# snes-bt.net
KiCad netlist of a schematic drawn in EAGLE
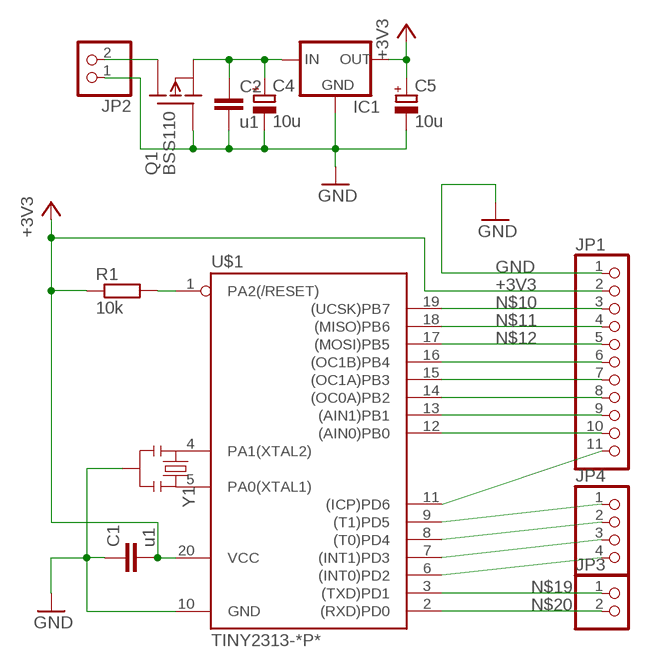
[diagram p0: schematic, sheet 1]

(export (version "E")
  (design (tool "Eeschema 10.0.6"))
  (components
    (comp (ref "C1")
      (value "u1")
      (footprint "eagle-import:C025-025X050")
      (libsource (lib "eagle-import") (part "C-EU025-025X050"))
    )
    (comp (ref "C2")
      (value "u1")
      (footprint "eagle-import:C025-025X050")
      (libsource (lib "eagle-import") (part "C-EU025-025X050"))
    )
    (comp (ref "C4")
      (value "10u")
      (footprint "eagle-import:E2,5-6E")
      (libsource (lib "eagle-import") (part "CPOL-EUE2,5-6E"))
    )
    (comp (ref "C5")
      (value "10u")
      (footprint "eagle-import:E2,5-6E")
      (libsource (lib "eagle-import") (part "CPOL-EUE2,5-6E"))
    )
    (comp (ref "IC1")
      (value "MCP1700_TO92-THIN")
      (footprint "eagle-import:TO-92")
      (libsource (lib "eagle-import") (part "MCP1700_TO92-THIN"))
    )
    (comp (ref "JP1")
      (value "PINHD-1X11")
      (footprint "eagle-import:1X11")
      (libsource (lib "eagle-import") (part "PINHD-1X11"))
    )
    (comp (ref "JP2")
      (value "PINHD-1X2")
      (footprint "eagle-import:1X02")
      (libsource (lib "eagle-import") (part "PINHD-1X2"))
    )
    (comp (ref "JP3")
      (value "PINHD-1X2")
      (footprint "eagle-import:1X02")
      (libsource (lib "eagle-import") (part "PINHD-1X2"))
    )
    (comp (ref "JP4")
      (value "PINHD-1X4")
      (footprint "eagle-import:1X04")
      (libsource (lib "eagle-import") (part "PINHD-1X4"))
    )
    (comp (ref "Q1")
      (value "BSS110")
      (footprint "eagle-import:TO92")
      (libsource (lib "eagle-import") (part "BSS110"))
    )
    (comp (ref "R1")
      (value "10k")
      (footprint "eagle-import:0204_7")
      (libsource (lib "eagle-import") (part "R-EU_0204/7"))
    )
    (comp (ref "U$1")
      (value "TINY2313-*P*")
      (footprint "eagle-import:DIL20")
      (libsource (lib "eagle-import") (part "TINY2313-P"))
    )
    (comp (ref "Y1")
      (value "RESONATORPTH")
      (footprint "eagle-import:RESONATOR-PTH")
      (libsource (lib "eagle-import") (part "RESONATORPTH"))
    )
  )
  (nets
    (net (code "1") (name "+3V3") (class "Default")
      (node (ref "C1") (pin "2") (pinfunction "2_2") (pintype "passive"))
      (node (ref "C5") (pin "+") (pinfunction "+_+") (pintype "passive"))
      (node (ref "IC1") (pin "3") (pinfunction "OUT_3") (pintype "passive"))
      (node (ref "JP1") (pin "2") (pinfunction "2_2") (pintype "passive"))
      (node (ref "R1") (pin "1") (pinfunction "1_1") (pintype "passive"))
      (node (ref "U$1") (pin "20") (pinfunction "VCC_20") (pintype "power_in"))
    )
    (net (code "2") (name "/N$10") (class "Default")
      (node (ref "JP1") (pin "3") (pinfunction "3_3") (pintype "passive"))
      (node (ref "U$1") (pin "19") (pinfunction "(UCSK)PB7_19") (pintype "bidirectional"))
    )
    (net (code "3") (name "/N$11") (class "Default")
      (node (ref "JP1") (pin "4") (pinfunction "4_4") (pintype "passive"))
      (node (ref "U$1") (pin "18") (pinfunction "(MISO)PB6_18") (pintype "bidirectional"))
    )
    (net (code "4") (name "/N$12") (class "Default")
      (node (ref "JP1") (pin "5") (pinfunction "5_5") (pintype "passive"))
      (node (ref "U$1") (pin "17") (pinfunction "(MOSI)PB5_17") (pintype "bidirectional"))
    )
    (net (code "5") (name "/N$19") (class "Default")
      (node (ref "JP3") (pin "1") (pinfunction "1_1") (pintype "passive"))
      (node (ref "U$1") (pin "3") (pinfunction "(TXD)PD1_3") (pintype "bidirectional"))
    )
    (net (code "6") (name "/N$20") (class "Default")
      (node (ref "JP3") (pin "2") (pinfunction "2_2") (pintype "passive"))
      (node (ref "U$1") (pin "2") (pinfunction "(RXD)PD0_2") (pintype "bidirectional"))
    )
    (net (code "7") (name "GND") (class "Default")
      (node (ref "C1") (pin "1") (pinfunction "1_1") (pintype "passive"))
      (node (ref "C2") (pin "2") (pinfunction "2_2") (pintype "passive"))
      (node (ref "C4") (pin "-") (pinfunction "-_-") (pintype "passive"))
      (node (ref "C5") (pin "-") (pinfunction "-_-") (pintype "passive"))
      (node (ref "IC1") (pin "1") (pinfunction "GND_1") (pintype "input"))
      (node (ref "JP1") (pin "1") (pinfunction "1_1") (pintype "passive"))
      (node (ref "JP2") (pin "1") (pinfunction "1_1") (pintype "passive"))
      (node (ref "Q1") (pin "2") (pinfunction "G_2") (pintype "passive"))
      (node (ref "U$1") (pin "10") (pinfunction "GND_10") (pintype "power_in"))
      (node (ref "Y1") (pin "2") (pinfunction "2_2") (pintype "passive"))
    )
    (net (code "8") (name "Net-(IC1-IN)") (class "Default")
      (node (ref "C2") (pin "1") (pinfunction "1_1") (pintype "passive"))
      (node (ref "C4") (pin "+") (pinfunction "+_+") (pintype "passive"))
      (node (ref "IC1") (pin "2") (pinfunction "IN_2") (pintype "input"))
      (node (ref "Q1") (pin "1") (pinfunction "S_1") (pintype "passive"))
    )
    (net (code "9") (name "Net-(Q1-D)") (class "Default")
      (node (ref "JP2") (pin "2") (pinfunction "2_2") (pintype "passive"))
      (node (ref "Q1") (pin "3") (pinfunction "D_3") (pintype "passive"))
    )
    (net (code "10") (name "Net-(U$1-(AIN0)PB0)") (class "Default")
      (node (ref "JP1") (pin "10") (pinfunction "10_10") (pintype "passive"))
      (node (ref "U$1") (pin "12") (pinfunction "(AIN0)PB0_12") (pintype "bidirectional"))
    )
    (net (code "11") (name "Net-(U$1-(AIN1)PB1)") (class "Default")
      (node (ref "JP1") (pin "9") (pinfunction "9_9") (pintype "passive"))
      (node (ref "U$1") (pin "13") (pinfunction "(AIN1)PB1_13") (pintype "bidirectional"))
    )
    (net (code "12") (name "Net-(U$1-(ICP)PD6)") (class "Default")
      (node (ref "JP1") (pin "11") (pinfunction "11_11") (pintype "passive"))
      (node (ref "U$1") (pin "11") (pinfunction "(ICP)PD6_11") (pintype "bidirectional"))
    )
    (net (code "13") (name "Net-(U$1-(INT0)PD2)") (class "Default")
      (node (ref "JP4") (pin "4") (pinfunction "4_4") (pintype "passive"))
      (node (ref "U$1") (pin "6") (pinfunction "(INT0)PD2_6") (pintype "bidirectional"))
    )
    (net (code "14") (name "Net-(U$1-(INT1)PD3)") (class "Default")
      (node (ref "JP4") (pin "3") (pinfunction "3_3") (pintype "passive"))
      (node (ref "U$1") (pin "7") (pinfunction "(INT1)PD3_7") (pintype "bidirectional"))
    )
    (net (code "15") (name "Net-(U$1-(OC0A)PB2)") (class "Default")
      (node (ref "JP1") (pin "8") (pinfunction "8_8") (pintype "passive"))
      (node (ref "U$1") (pin "14") (pinfunction "(OC0A)PB2_14") (pintype "bidirectional"))
    )
    (net (code "16") (name "Net-(U$1-(OC1A)PB3)") (class "Default")
      (node (ref "JP1") (pin "7") (pinfunction "7_7") (pintype "passive"))
      (node (ref "U$1") (pin "15") (pinfunction "(OC1A)PB3_15") (pintype "bidirectional"))
    )
    (net (code "17") (name "Net-(U$1-(OC1B)PB4)") (class "Default")
      (node (ref "JP1") (pin "6") (pinfunction "6_6") (pintype "passive"))
      (node (ref "U$1") (pin "16") (pinfunction "(OC1B)PB4_16") (pintype "bidirectional"))
    )
    (net (code "18") (name "Net-(U$1-(T0)PD4)") (class "Default")
      (node (ref "JP4") (pin "2") (pinfunction "2_2") (pintype "passive"))
      (node (ref "U$1") (pin "8") (pinfunction "(T0)PD4_8") (pintype "bidirectional"))
    )
    (net (code "19") (name "Net-(U$1-(T1)PD5)") (class "Default")
      (node (ref "JP4") (pin "1") (pinfunction "1_1") (pintype "passive"))
      (node (ref "U$1") (pin "9") (pinfunction "(T1)PD5_9") (pintype "bidirectional"))
    )
    (net (code "20") (name "Net-(U$1-PA0(XTAL1))") (class "Default")
      (node (ref "U$1") (pin "5") (pinfunction "PA0(XTAL1)_5") (pintype "bidirectional"))
      (node (ref "Y1") (pin "3") (pinfunction "3_3") (pintype "passive"))
    )
    (net (code "21") (name "Net-(U$1-PA1(XTAL2))") (class "Default")
      (node (ref "U$1") (pin "4") (pinfunction "PA1(XTAL2)_4") (pintype "bidirectional"))
      (node (ref "Y1") (pin "1") (pinfunction "1_1") (pintype "passive"))
    )
    (net (code "22") (name "Net-(U$1-PA2({slash}RESET))") (class "Default")
      (node (ref "R1") (pin "2") (pinfunction "2_2") (pintype "passive"))
      (node (ref "U$1") (pin "1") (pinfunction "PA2(/RESET)_1") (pintype "input"))
    )
  )
)
